# CellSelectModule.net
KiCad netlist of a schematic drawn in Altium Designer
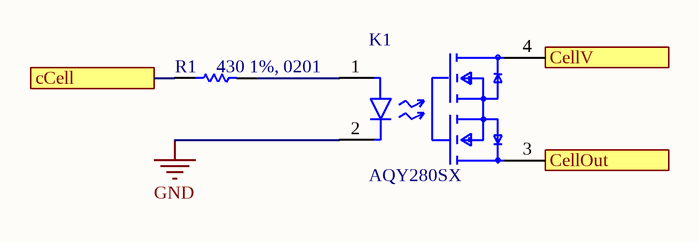
[diagram p0: CellSelectModule.SchDoc]

(export (version "E")
  (design (tool "Eeschema 10.0.6"))
  (components
    (comp (ref "K1")
      (value "AQY280SX")
      (footprint "FP-AQY280SX-MFG")
      (description "AQY280SX AQY Photomos Series 120 mA 350 V 25 Ohm SMT 1 Channel Solid State Relay -SOP-4")
      (libsource (lib "Altium Content Vault") (part "39108d2c2fe9c6c4263f1aa8ae40286"))
    )
    (comp (ref "R1")
      (value "430 1%, 0201")
      (footprint "RESC0603X26X15NL03T05")
      (fields (field (name "MANUFACTURER") "Panasonic") (field (name "PART NUMBER") "ERJ1GNF4302C"))
      (libsource (lib "Altium Content Vault") (part "RES"))
    )
  )
  (nets
    (net (code "1") (name "/CellOut") (class "Default")
      (node (ref "K1") (pin "3") (pinfunction "1_DRAIN_3") (pintype "passive"))
    )
    (net (code "2") (name "/CellV") (class "Default")
      (node (ref "K1") (pin "4") (pinfunction "2_DRAIN_4") (pintype "passive"))
    )
    (net (code "3") (name "/cCell") (class "Default")
      (node (ref "R1") (pin "1") (pinfunction "1_1") (pintype "passive"))
    )
    (net (code "4") (name "GND") (class "Default")
      (node (ref "K1") (pin "2") (pinfunction "C_2") (pintype "passive"))
    )
    (net (code "5") (name "Net-(K1-A)") (class "Default")
      (node (ref "K1") (pin "1") (pinfunction "A_1") (pintype "passive"))
      (node (ref "R1") (pin "2") (pinfunction "2_2") (pintype "passive"))
    )
  )
)
